# STLINK.net
KiCad netlist of a schematic drawn in Altium Designer
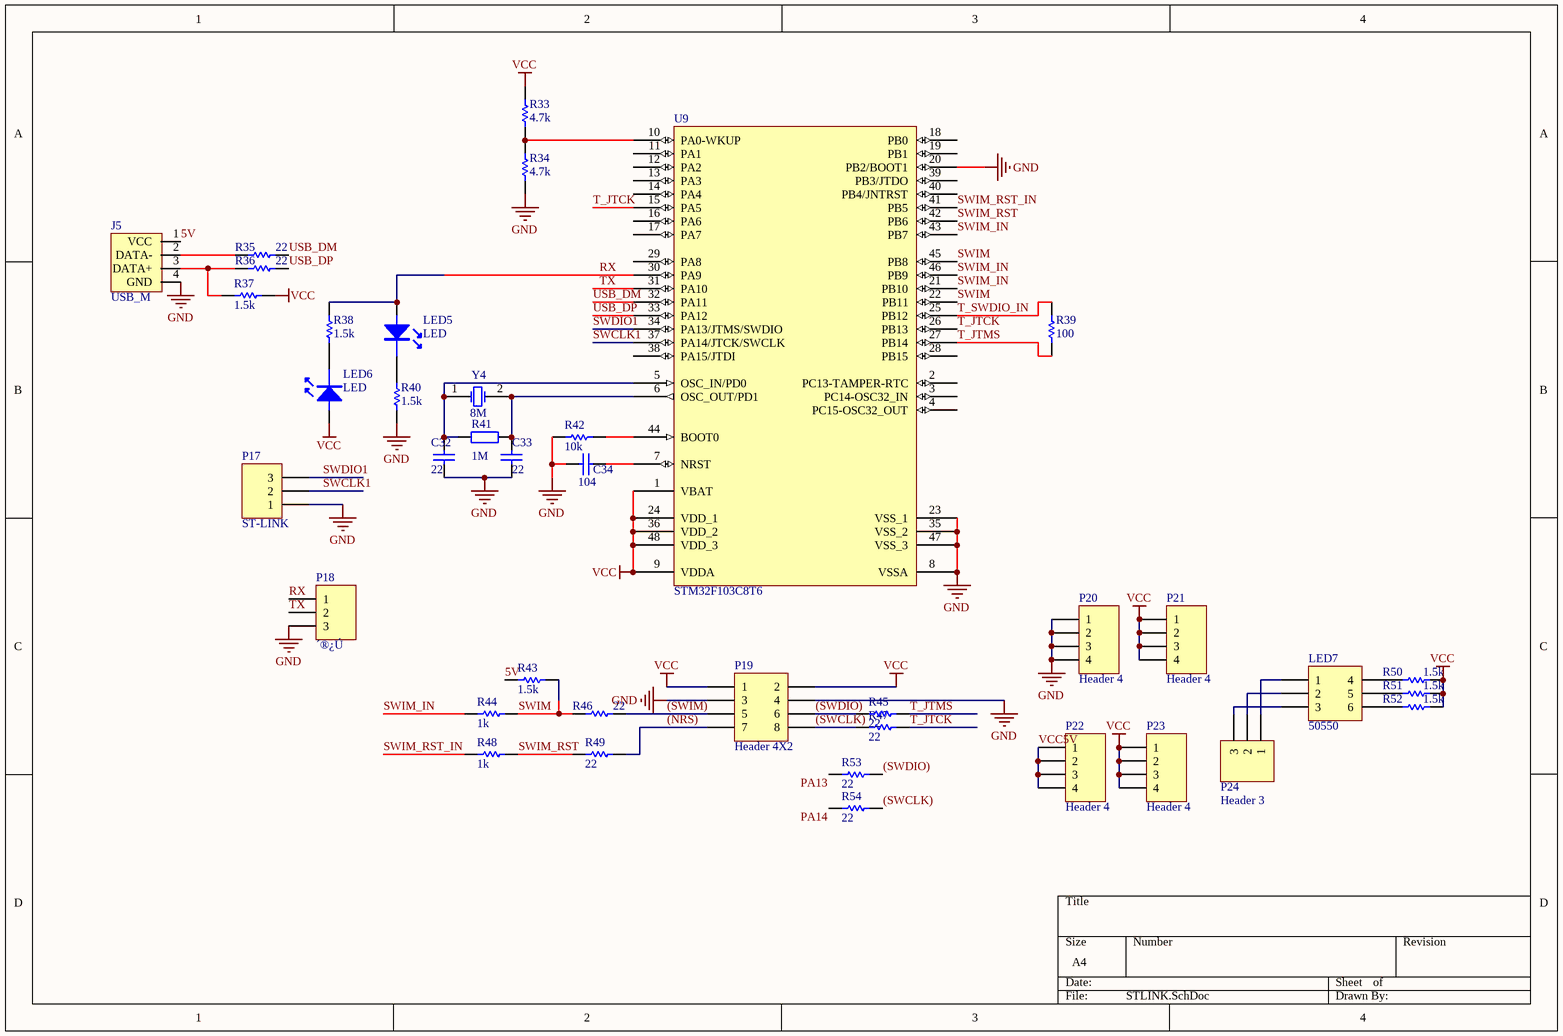
[diagram p0: STLINK.SchDoc]

(export (version "E")
  (design (tool "Eeschema 10.0.6"))
  (components
    (comp (ref "C32")
      (value "22")
      (footprint "6-0805_N")
      (description "Capacitor")
      (fields (field (name "Comment") "Cap") (field (name "PUBLISHER") "Altium Limited"))
      (libsource (lib "Miscellaneous Devices") (part "Cap"))
    )
    (comp (ref "C33")
      (value "22")
      (footprint "6-0805_N")
      (description "Capacitor")
      (fields (field (name "Comment") "Cap") (field (name "PUBLISHER") "Altium Limited"))
      (libsource (lib "Miscellaneous Devices") (part "Cap"))
    )
    (comp (ref "C34")
      (value "104")
      (footprint "6-0805_N")
      (fields (field (name "Comment") "Cap"))
      (libsource (lib "WK_PCB") (part "Cap"))
    )
    (comp (ref "J5") (value "USB_M") (footprint "USB MICRO") (libsource (lib "SCH封装库") (part "USB_M")))
    (comp (ref "LED5") (value "LED") (footprint "6-0805_N") (libsource (lib "WK_PCB") (part "LED")))
    (comp (ref "LED6") (value "LED") (footprint "6-0805_N") (libsource (lib "WK_PCB") (part "LED")))
    (comp (ref "LED7")
      (value "50550")
      (footprint "led5050")
      (description "Header, 3-Pin, Dual row")
      (fields (field (name "PUBLISHER") "Altium Limited"))
      (libsource (lib "Miscellaneous Connectors") (part "Header 3X2A"))
    )
    (comp (ref "P17")
      (value "ST-LINK")
      (footprint "HDR1X3")
      (description "Header, 3-Pin")
      (fields (field (name "PUBLISHER") "Altium Limited"))
      (libsource (lib "") (part "Header 3_1"))
    )
    (comp (ref "P18")
      (value "串口")
      (footprint "HDR1X3")
      (description "Header, 3-Pin")
      (fields (field (name "PUBLISHER") "Altium Limited"))
      (libsource (lib "") (part "Header 3_2"))
    )
    (comp (ref "P19")
      (value "Header 4X2")
      (footprint "HDR2X4")
      (description "Header, 4-Pin, Dual row")
      (fields (field (name "PUBLISHER") "Altium Limited"))
      (libsource (lib "Miscellaneous Connectors") (part "Header 4X2"))
    )
    (comp (ref "P20")
      (value "Header 4")
      (footprint "HDR1X4")
      (description "Header, 4-Pin")
      (fields (field (name "PUBLISHER") "Altium Limited"))
      (libsource (lib "Miscellaneous Connectors") (part "Header 4"))
    )
    (comp (ref "P21")
      (value "Header 4")
      (footprint "HDR1X4")
      (description "Header, 4-Pin")
      (fields (field (name "PUBLISHER") "Altium Limited"))
      (libsource (lib "Miscellaneous Connectors") (part "Header 4"))
    )
    (comp (ref "P22")
      (value "Header 4")
      (footprint "HDR1X4")
      (description "Header, 4-Pin")
      (fields (field (name "PUBLISHER") "Altium Limited"))
      (libsource (lib "Miscellaneous Connectors") (part "Header 4"))
    )
    (comp (ref "P23")
      (value "Header 4")
      (footprint "HDR1X4")
      (description "Header, 4-Pin")
      (fields (field (name "PUBLISHER") "Altium Limited"))
      (libsource (lib "Miscellaneous Connectors") (part "Header 4"))
    )
    (comp (ref "P24")
      (value "Header 3")
      (footprint "HDR1X3")
      (description "Header, 3-Pin")
      (fields (field (name "PUBLISHER") "Altium Limited"))
      (libsource (lib "Miscellaneous Connectors") (part "Header 3"))
    )
    (comp (ref "R33")
      (value "4.7k")
      (footprint "6-0805_N")
      (fields (field (name "Comment") "RES"))
      (libsource (lib "WK_PCB") (part "RES"))
    )
    (comp (ref "R34")
      (value "4.7k")
      (footprint "6-0805_N")
      (fields (field (name "Comment") "RES"))
      (libsource (lib "WK_PCB") (part "RES"))
    )
    (comp (ref "R35")
      (value "22")
      (footprint "6-0805_N")
      (fields (field (name "Comment") "RES"))
      (libsource (lib "WK_PCB") (part "RES"))
    )
    (comp (ref "R36")
      (value "22")
      (footprint "6-0805_N")
      (fields (field (name "Comment") "RES"))
      (libsource (lib "WK_PCB") (part "RES"))
    )
    (comp (ref "R37")
      (value "1.5k")
      (footprint "6-0805_N")
      (fields (field (name "Comment") "RES"))
      (libsource (lib "WK_PCB") (part "RES"))
    )
    (comp (ref "R38")
      (value "1.5k")
      (footprint "6-0805_N")
      (fields (field (name "Comment") "RES"))
      (libsource (lib "WK_PCB") (part "RES"))
    )
    (comp (ref "R39")
      (value "100")
      (footprint "6-0805_N")
      (fields (field (name "Comment") "RES"))
      (libsource (lib "WK_PCB") (part "RES"))
    )
    (comp (ref "R40")
      (value "1.5k")
      (footprint "6-0805_N")
      (fields (field (name "Comment") "RES"))
      (libsource (lib "WK_PCB") (part "RES"))
    )
    (comp (ref "R41")
      (value "1M")
      (footprint "6-0805_N")
      (description "Resistor")
      (fields (field (name "Comment") "Res2") (field (name "PUBLISHER") "Altium Limited"))
      (libsource (lib "Miscellaneous Devices") (part "Res2"))
    )
    (comp (ref "R42")
      (value "10k")
      (footprint "6-0805_N")
      (fields (field (name "Comment") "RES"))
      (libsource (lib "WK_PCB") (part "RES"))
    )
    (comp (ref "R43")
      (value "1.5k")
      (footprint "6-0805_N")
      (fields (field (name "Comment") "RES"))
      (libsource (lib "WK_PCB") (part "RES"))
    )
    (comp (ref "R44")
      (value "1k")
      (footprint "6-0805_N")
      (fields (field (name "Comment") "RES"))
      (libsource (lib "WK_PCB") (part "RES"))
    )
    (comp (ref "R45")
      (value "22")
      (footprint "6-0805_N")
      (fields (field (name "Comment") "RES"))
      (libsource (lib "WK_PCB") (part "RES"))
    )
    (comp (ref "R46")
      (value "22")
      (footprint "6-0805_N")
      (fields (field (name "Comment") "RES"))
      (libsource (lib "WK_PCB") (part "RES"))
    )
    (comp (ref "R47")
      (value "22")
      (footprint "6-0805_N")
      (fields (field (name "Comment") "RES"))
      (libsource (lib "WK_PCB") (part "RES"))
    )
    (comp (ref "R48")
      (value "1k")
      (footprint "6-0805_N")
      (fields (field (name "Comment") "RES"))
      (libsource (lib "WK_PCB") (part "RES"))
    )
    (comp (ref "R49")
      (value "22")
      (footprint "6-0805_N")
      (fields (field (name "Comment") "RES"))
      (libsource (lib "WK_PCB") (part "RES"))
    )
    (comp (ref "R50")
      (value "1.5k")
      (footprint "6-0805_N")
      (fields (field (name "Comment") "RES"))
      (libsource (lib "WK_PCB") (part "RES"))
    )
    (comp (ref "R51")
      (value "1.5k")
      (footprint "6-0805_N")
      (fields (field (name "Comment") "RES"))
      (libsource (lib "WK_PCB") (part "RES"))
    )
    (comp (ref "R52")
      (value "1.5k")
      (footprint "6-0805_N")
      (fields (field (name "Comment") "RES"))
      (libsource (lib "WK_PCB") (part "RES"))
    )
    (comp (ref "R53")
      (value "22")
      (footprint "1608[0603]")
      (fields (field (name "Comment") "RES"))
      (libsource (lib "WK_PCB") (part "RES"))
    )
    (comp (ref "R54")
      (value "22")
      (footprint "1608[0603]")
      (fields (field (name "Comment") "RES"))
      (libsource (lib "WK_PCB") (part "RES"))
    )
    (comp (ref "U9")
      (value "STM32F103C8T6")
      (footprint "LQFP48S")
      (description "STM32 ARM-based 32-bit MCU with 64 Kbytes Flash, 48-pin LQFP, Industrial Temperature")
      (fields (field (name "PUBLISHER") "Altium Limited"))
      (libsource (lib "ST Microcontroller 32-Bit STM32") (part "STM32F103C8T6"))
    )
    (comp (ref "Y4") (value "8M") (footprint "晶振") (libsource (lib "SCH封装库") (part "晶振")))
  )
  (nets
    (net (code "1") (name "/(NRS)") (class "Default")
      (node (ref "P19") (pin "7") (pinfunction "7_7") (pintype "passive"))
      (node (ref "R49") (pin "1") (pinfunction "1_1") (pintype "passive"))
    )
    (net (code "2") (name "/(SWCLK)") (class "Default")
      (node (ref "P19") (pin "8") (pinfunction "8_8") (pintype "passive"))
      (node (ref "R47") (pin "1") (pinfunction "1_1") (pintype "passive"))
      (node (ref "R54") (pin "2") (pinfunction "2_2") (pintype "passive"))
    )
    (net (code "3") (name "/(SWDIO)") (class "Default")
      (node (ref "P19") (pin "6") (pinfunction "6_6") (pintype "passive"))
      (node (ref "R45") (pin "1") (pinfunction "1_1") (pintype "passive"))
      (node (ref "R53") (pin "2") (pinfunction "2_2") (pintype "passive"))
    )
    (net (code "4") (name "/(SWIM)") (class "Default")
      (node (ref "P19") (pin "5") (pinfunction "5_5") (pintype "passive"))
      (node (ref "R46") (pin "1") (pinfunction "1_1") (pintype "passive"))
    )
    (net (code "5") (name "/5V") (class "Default")
      (node (ref "J5") (pin "1") (pinfunction "VCC_1") (pintype "passive"))
      (node (ref "R43") (pin "1") (pinfunction "1_1") (pintype "passive"))
    )
    (net (code "6") (name "/PA13") (class "Default")
      (node (ref "R53") (pin "1") (pinfunction "1_1") (pintype "passive"))
    )
    (net (code "7") (name "/PA14") (class "Default")
      (node (ref "R54") (pin "1") (pinfunction "1_1") (pintype "passive"))
    )
    (net (code "8") (name "/RX") (class "Default")
      (node (ref "LED5") (pin "1") (pinfunction "A_1") (pintype "passive"))
      (node (ref "P18") (pin "1") (pinfunction "1_1") (pintype "passive"))
      (node (ref "R38") (pin "2") (pinfunction "2_2") (pintype "passive"))
      (node (ref "U9") (pin "30") (pinfunction "PA9_30") (pintype "bidirectional"))
    )
    (net (code "9") (name "/SWCLK1") (class "Default")
      (node (ref "P17") (pin "2") (pinfunction "2_2") (pintype "passive"))
      (node (ref "U9") (pin "37") (pinfunction "PA14/JTCK/SWCLK_37") (pintype "bidirectional"))
    )
    (net (code "10") (name "/SWDIO1") (class "Default")
      (node (ref "P17") (pin "3") (pinfunction "3_3") (pintype "passive"))
      (node (ref "U9") (pin "34") (pinfunction "PA13/JTMS/SWDIO_34") (pintype "bidirectional"))
    )
    (net (code "11") (name "/SWIM") (class "Default")
      (node (ref "R43") (pin "2") (pinfunction "2_2") (pintype "passive"))
      (node (ref "R44") (pin "2") (pinfunction "2_2") (pintype "passive"))
      (node (ref "R46") (pin "2") (pinfunction "2_2") (pintype "passive"))
      (node (ref "U9") (pin "22") (pinfunction "PB11_22") (pintype "bidirectional"))
      (node (ref "U9") (pin "45") (pinfunction "PB8_45") (pintype "bidirectional"))
    )
    (net (code "12") (name "/SWIM_IN") (class "Default")
      (node (ref "R44") (pin "1") (pinfunction "1_1") (pintype "passive"))
      (node (ref "U9") (pin "21") (pinfunction "PB10_21") (pintype "bidirectional"))
      (node (ref "U9") (pin "43") (pinfunction "PB7_43") (pintype "bidirectional"))
      (node (ref "U9") (pin "46") (pinfunction "PB9_46") (pintype "bidirectional"))
    )
    (net (code "13") (name "/SWIM_RST") (class "Default")
      (node (ref "R48") (pin "2") (pinfunction "2_2") (pintype "passive"))
      (node (ref "R49") (pin "2") (pinfunction "2_2") (pintype "passive"))
      (node (ref "U9") (pin "42") (pinfunction "PB6_42") (pintype "bidirectional"))
    )
    (net (code "14") (name "/SWIM_RST_IN") (class "Default")
      (node (ref "R48") (pin "1") (pinfunction "1_1") (pintype "passive"))
      (node (ref "U9") (pin "41") (pinfunction "PB5_41") (pintype "bidirectional"))
    )
    (net (code "15") (name "/TX") (class "Default")
      (node (ref "P18") (pin "2") (pinfunction "2_2") (pintype "passive"))
      (node (ref "U9") (pin "31") (pinfunction "PA10_31") (pintype "bidirectional"))
    )
    (net (code "16") (name "/T_JTCK") (class "Default")
      (node (ref "R47") (pin "2") (pinfunction "2_2") (pintype "passive"))
      (node (ref "U9") (pin "15") (pinfunction "PA5_15") (pintype "bidirectional"))
      (node (ref "U9") (pin "26") (pinfunction "PB13_26") (pintype "bidirectional"))
    )
    (net (code "17") (name "/T_JTMS") (class "Default")
      (node (ref "R39") (pin "1") (pinfunction "1_1") (pintype "passive"))
      (node (ref "R45") (pin "2") (pinfunction "2_2") (pintype "passive"))
      (node (ref "U9") (pin "27") (pinfunction "PB14_27") (pintype "bidirectional"))
    )
    (net (code "18") (name "/T_SWDIO_IN") (class "Default")
      (node (ref "R39") (pin "2") (pinfunction "2_2") (pintype "passive"))
      (node (ref "U9") (pin "25") (pinfunction "PB12_25") (pintype "bidirectional"))
    )
    (net (code "19") (name "/USB_DM") (class "Default")
      (node (ref "R35") (pin "2") (pinfunction "2_2") (pintype "passive"))
      (node (ref "U9") (pin "32") (pinfunction "PA11_32") (pintype "bidirectional"))
    )
    (net (code "20") (name "/USB_DP") (class "Default")
      (node (ref "R36") (pin "2") (pinfunction "2_2") (pintype "passive"))
      (node (ref "U9") (pin "33") (pinfunction "PA12_33") (pintype "bidirectional"))
    )
    (net (code "21") (name "/VCC5V") (class "Default")
      (node (ref "P22") (pin "1") (pinfunction "1_1") (pintype "passive"))
      (node (ref "P22") (pin "2") (pinfunction "2_2") (pintype "passive"))
      (node (ref "P22") (pin "3") (pinfunction "3_3") (pintype "passive"))
      (node (ref "P22") (pin "4") (pinfunction "4_4") (pintype "passive"))
    )
    (net (code "22") (name "GND") (class "Default")
      (node (ref "C32") (pin "1") (pinfunction "1_1") (pintype "passive"))
      (node (ref "C33") (pin "1") (pinfunction "1_1") (pintype "passive"))
      (node (ref "C34") (pin "1") (pinfunction "1_1") (pintype "passive"))
      (node (ref "J5") (pin "4") (pinfunction "GND_4") (pintype "passive"))
      (node (ref "P17") (pin "1") (pinfunction "1_1") (pintype "passive"))
      (node (ref "P18") (pin "3") (pinfunction "3_3") (pintype "passive"))
      (node (ref "P19") (pin "3") (pinfunction "3_3") (pintype "passive"))
      (node (ref "P19") (pin "4") (pinfunction "4_4") (pintype "passive"))
      (node (ref "P20") (pin "1") (pinfunction "1_1") (pintype "passive"))
      (node (ref "P20") (pin "2") (pinfunction "2_2") (pintype "passive"))
      (node (ref "P20") (pin "3") (pinfunction "3_3") (pintype "passive"))
      (node (ref "P20") (pin "4") (pinfunction "4_4") (pintype "passive"))
      (node (ref "R34") (pin "1") (pinfunction "1_1") (pintype "passive"))
      (node (ref "R40") (pin "1") (pinfunction "1_1") (pintype "passive"))
      (node (ref "R42") (pin "1") (pinfunction "1_1") (pintype "passive"))
      (node (ref "U9") (pin "20") (pinfunction "PB2/BOOT1_20") (pintype "bidirectional"))
      (node (ref "U9") (pin "23") (pinfunction "VSS_1_23") (pintype "power_in"))
      (node (ref "U9") (pin "35") (pinfunction "VSS_2_35") (pintype "power_in"))
      (node (ref "U9") (pin "47") (pinfunction "VSS_3_47") (pintype "power_in"))
      (node (ref "U9") (pin "8") (pinfunction "VSSA_8") (pintype "power_in"))
    )
    (net (code "23") (name "Net-(J5-DATA+)") (class "Default")
      (node (ref "J5") (pin "3") (pinfunction "DATA+_3") (pintype "passive"))
      (node (ref "R36") (pin "1") (pinfunction "1_1") (pintype "passive"))
      (node (ref "R37") (pin "1") (pinfunction "1_1") (pintype "passive"))
    )
    (net (code "24") (name "Net-(J5-DATA-)") (class "Default")
      (node (ref "J5") (pin "2") (pinfunction "DATA-_2") (pintype "passive"))
      (node (ref "R35") (pin "1") (pinfunction "1_1") (pintype "passive"))
    )
    (net (code "25") (name "Net-(LED5-K)") (class "Default")
      (node (ref "LED5") (pin "2") (pinfunction "K_2") (pintype "passive"))
      (node (ref "R40") (pin "2") (pinfunction "2_2") (pintype "passive"))
    )
    (net (code "26") (name "Net-(LED6-K)") (class "Default")
      (node (ref "LED6") (pin "2") (pinfunction "K_2") (pintype "passive"))
      (node (ref "R38") (pin "1") (pinfunction "1_1") (pintype "passive"))
    )
    (net (code "27") (name "Net-(LED7-Pad1)") (class "Default")
      (node (ref "LED7") (pin "1") (pinfunction "1_1") (pintype "passive"))
      (node (ref "P24") (pin "1") (pinfunction "1_1") (pintype "passive"))
    )
    (net (code "28") (name "Net-(LED7-Pad2)") (class "Default")
      (node (ref "LED7") (pin "2") (pinfunction "2_2") (pintype "passive"))
      (node (ref "P24") (pin "2") (pinfunction "2_2") (pintype "passive"))
    )
    (net (code "29") (name "Net-(LED7-Pad3)") (class "Default")
      (node (ref "LED7") (pin "3") (pinfunction "3_3") (pintype "passive"))
      (node (ref "P24") (pin "3") (pinfunction "3_3") (pintype "passive"))
    )
    (net (code "30") (name "Net-(LED7-Pad4)") (class "Default")
      (node (ref "LED7") (pin "4") (pinfunction "4_4") (pintype "passive"))
      (node (ref "R50") (pin "2") (pinfunction "2_2") (pintype "passive"))
    )
    (net (code "31") (name "Net-(LED7-Pad5)") (class "Default")
      (node (ref "LED7") (pin "5") (pinfunction "5_5") (pintype "passive"))
      (node (ref "R51") (pin "2") (pinfunction "2_2") (pintype "passive"))
    )
    (net (code "32") (name "Net-(LED7-Pad6)") (class "Default")
      (node (ref "LED7") (pin "6") (pinfunction "6_6") (pintype "passive"))
      (node (ref "R52") (pin "2") (pinfunction "2_2") (pintype "passive"))
    )
    (net (code "33") (name "Net-(U9-BOOT0)") (class "Default")
      (node (ref "R42") (pin "2") (pinfunction "2_2") (pintype "passive"))
      (node (ref "U9") (pin "44") (pinfunction "BOOT0_44") (pintype "input"))
    )
    (net (code "34") (name "Net-(U9-NRST)") (class "Default")
      (node (ref "C34") (pin "2") (pinfunction "2_2") (pintype "passive"))
      (node (ref "U9") (pin "7") (pinfunction "NRST_7") (pintype "bidirectional"))
    )
    (net (code "35") (name "Net-(U9-OSC_IN{slash}PD0)") (class "Default")
      (node (ref "C32") (pin "2") (pinfunction "2_2") (pintype "passive"))
      (node (ref "R41") (pin "1") (pinfunction "1_1") (pintype "passive"))
      (node (ref "U9") (pin "5") (pinfunction "OSC_IN/PD0_5") (pintype "input"))
      (node (ref "Y4") (pin "1") (pinfunction "OSC1_1") (pintype "passive"))
    )
    (net (code "36") (name "Net-(U9-OSC_OUT{slash}PD1)") (class "Default")
      (node (ref "C33") (pin "2") (pinfunction "2_2") (pintype "passive"))
      (node (ref "R41") (pin "2") (pinfunction "2_2") (pintype "passive"))
      (node (ref "U9") (pin "6") (pinfunction "OSC_OUT/PD1_6") (pintype "output"))
      (node (ref "Y4") (pin "2") (pinfunction "OSC2_2") (pintype "passive"))
    )
    (net (code "37") (name "Net-(U9-PA0-WKUP)") (class "Default")
      (node (ref "R33") (pin "1") (pinfunction "1_1") (pintype "passive"))
      (node (ref "R34") (pin "2") (pinfunction "2_2") (pintype "passive"))
      (node (ref "U9") (pin "10") (pinfunction "PA0-WKUP_10") (pintype "bidirectional"))
    )
    (net (code "38") (name "VCC") (class "Default")
      (node (ref "LED6") (pin "1") (pinfunction "A_1") (pintype "passive"))
      (node (ref "P19") (pin "1") (pinfunction "1_1") (pintype "passive"))
      (node (ref "P19") (pin "2") (pinfunction "2_2") (pintype "passive"))
      (node (ref "P21") (pin "1") (pinfunction "1_1") (pintype "passive"))
      (node (ref "P21") (pin "2") (pinfunction "2_2") (pintype "passive"))
      (node (ref "P21") (pin "3") (pinfunction "3_3") (pintype "passive"))
      (node (ref "P21") (pin "4") (pinfunction "4_4") (pintype "passive"))
      (node (ref "P23") (pin "1") (pinfunction "1_1") (pintype "passive"))
      (node (ref "P23") (pin "2") (pinfunction "2_2") (pintype "passive"))
      (node (ref "P23") (pin "3") (pinfunction "3_3") (pintype "passive"))
      (node (ref "P23") (pin "4") (pinfunction "4_4") (pintype "passive"))
      (node (ref "R33") (pin "2") (pinfunction "2_2") (pintype "passive"))
      (node (ref "R37") (pin "2") (pinfunction "2_2") (pintype "passive"))
      (node (ref "R50") (pin "1") (pinfunction "1_1") (pintype "passive"))
      (node (ref "R51") (pin "1") (pinfunction "1_1") (pintype "passive"))
      (node (ref "R52") (pin "1") (pinfunction "1_1") (pintype "passive"))
      (node (ref "U9") (pin "1") (pinfunction "VBAT_1") (pintype "power_in"))
      (node (ref "U9") (pin "24") (pinfunction "VDD_1_24") (pintype "power_in"))
      (node (ref "U9") (pin "36") (pinfunction "VDD_2_36") (pintype "power_in"))
      (node (ref "U9") (pin "48") (pinfunction "VDD_3_48") (pintype "power_in"))
      (node (ref "U9") (pin "9") (pinfunction "VDDA_9") (pintype "power_in"))
    )
    (net (code "39") (name "unconnected-(U9-PA1-Pad11)") (class "Default")
      (node (ref "U9") (pin "11") (pinfunction "PA1_11") (pintype "bidirectional"))
    )
    (net (code "40") (name "unconnected-(U9-PA2-Pad12)") (class "Default")
      (node (ref "U9") (pin "12") (pinfunction "PA2_12") (pintype "bidirectional"))
    )
    (net (code "41") (name "unconnected-(U9-PA3-Pad13)") (class "Default")
      (node (ref "U9") (pin "13") (pinfunction "PA3_13") (pintype "bidirectional"))
    )
    (net (code "42") (name "unconnected-(U9-PA4-Pad14)") (class "Default")
      (node (ref "U9") (pin "14") (pinfunction "PA4_14") (pintype "bidirectional"))
    )
    (net (code "43") (name "unconnected-(U9-PA6-Pad16)") (class "Default")
      (node (ref "U9") (pin "16") (pinfunction "PA6_16") (pintype "bidirectional"))
    )
    (net (code "44") (name "unconnected-(U9-PA7-Pad17)") (class "Default")
      (node (ref "U9") (pin "17") (pinfunction "PA7_17") (pintype "bidirectional"))
    )
    (net (code "45") (name "unconnected-(U9-PA8-Pad29)") (class "Default")
      (node (ref "U9") (pin "29") (pinfunction "PA8_29") (pintype "bidirectional"))
    )
    (net (code "46") (name "unconnected-(U9-PA15{slash}JTDI-Pad38)") (class "Default")
      (node (ref "U9") (pin "38") (pinfunction "PA15/JTDI_38") (pintype "bidirectional"))
    )
    (net (code "47") (name "unconnected-(U9-PB0-Pad18)") (class "Default")
      (node (ref "U9") (pin "18") (pinfunction "PB0_18") (pintype "bidirectional"))
    )
    (net (code "48") (name "unconnected-(U9-PB1-Pad19)") (class "Default")
      (node (ref "U9") (pin "19") (pinfunction "PB1_19") (pintype "bidirectional"))
    )
    (net (code "49") (name "unconnected-(U9-PB3{slash}JTDO-Pad39)") (class "Default")
      (node (ref "U9") (pin "39") (pinfunction "PB3/JTDO_39") (pintype "bidirectional"))
    )
    (net (code "50") (name "unconnected-(U9-PB4{slash}JNTRST-Pad40)") (class "Default")
      (node (ref "U9") (pin "40") (pinfunction "PB4/JNTRST_40") (pintype "bidirectional"))
    )
    (net (code "51") (name "unconnected-(U9-PB15-Pad28)") (class "Default")
      (node (ref "U9") (pin "28") (pinfunction "PB15_28") (pintype "bidirectional"))
    )
    (net (code "52") (name "unconnected-(U9-PC13-TAMPER-RTC-Pad2)") (class "Default")
      (node (ref "U9") (pin "2") (pinfunction "PC13-TAMPER-RTC_2") (pintype "bidirectional"))
    )
    (net (code "53") (name "unconnected-(U9-PC14-OSC32_IN-Pad3)") (class "Default")
      (node (ref "U9") (pin "3") (pinfunction "PC14-OSC32_IN_3") (pintype "bidirectional"))
    )
    (net (code "54") (name "unconnected-(U9-PC15-OSC32_OUT-Pad4)") (class "Default")
      (node (ref "U9") (pin "4") (pinfunction "PC15-OSC32_OUT_4") (pintype "bidirectional"))
    )
  )
)
